# Sheet1.net
KiCad netlist of a schematic drawn in Altium Designer
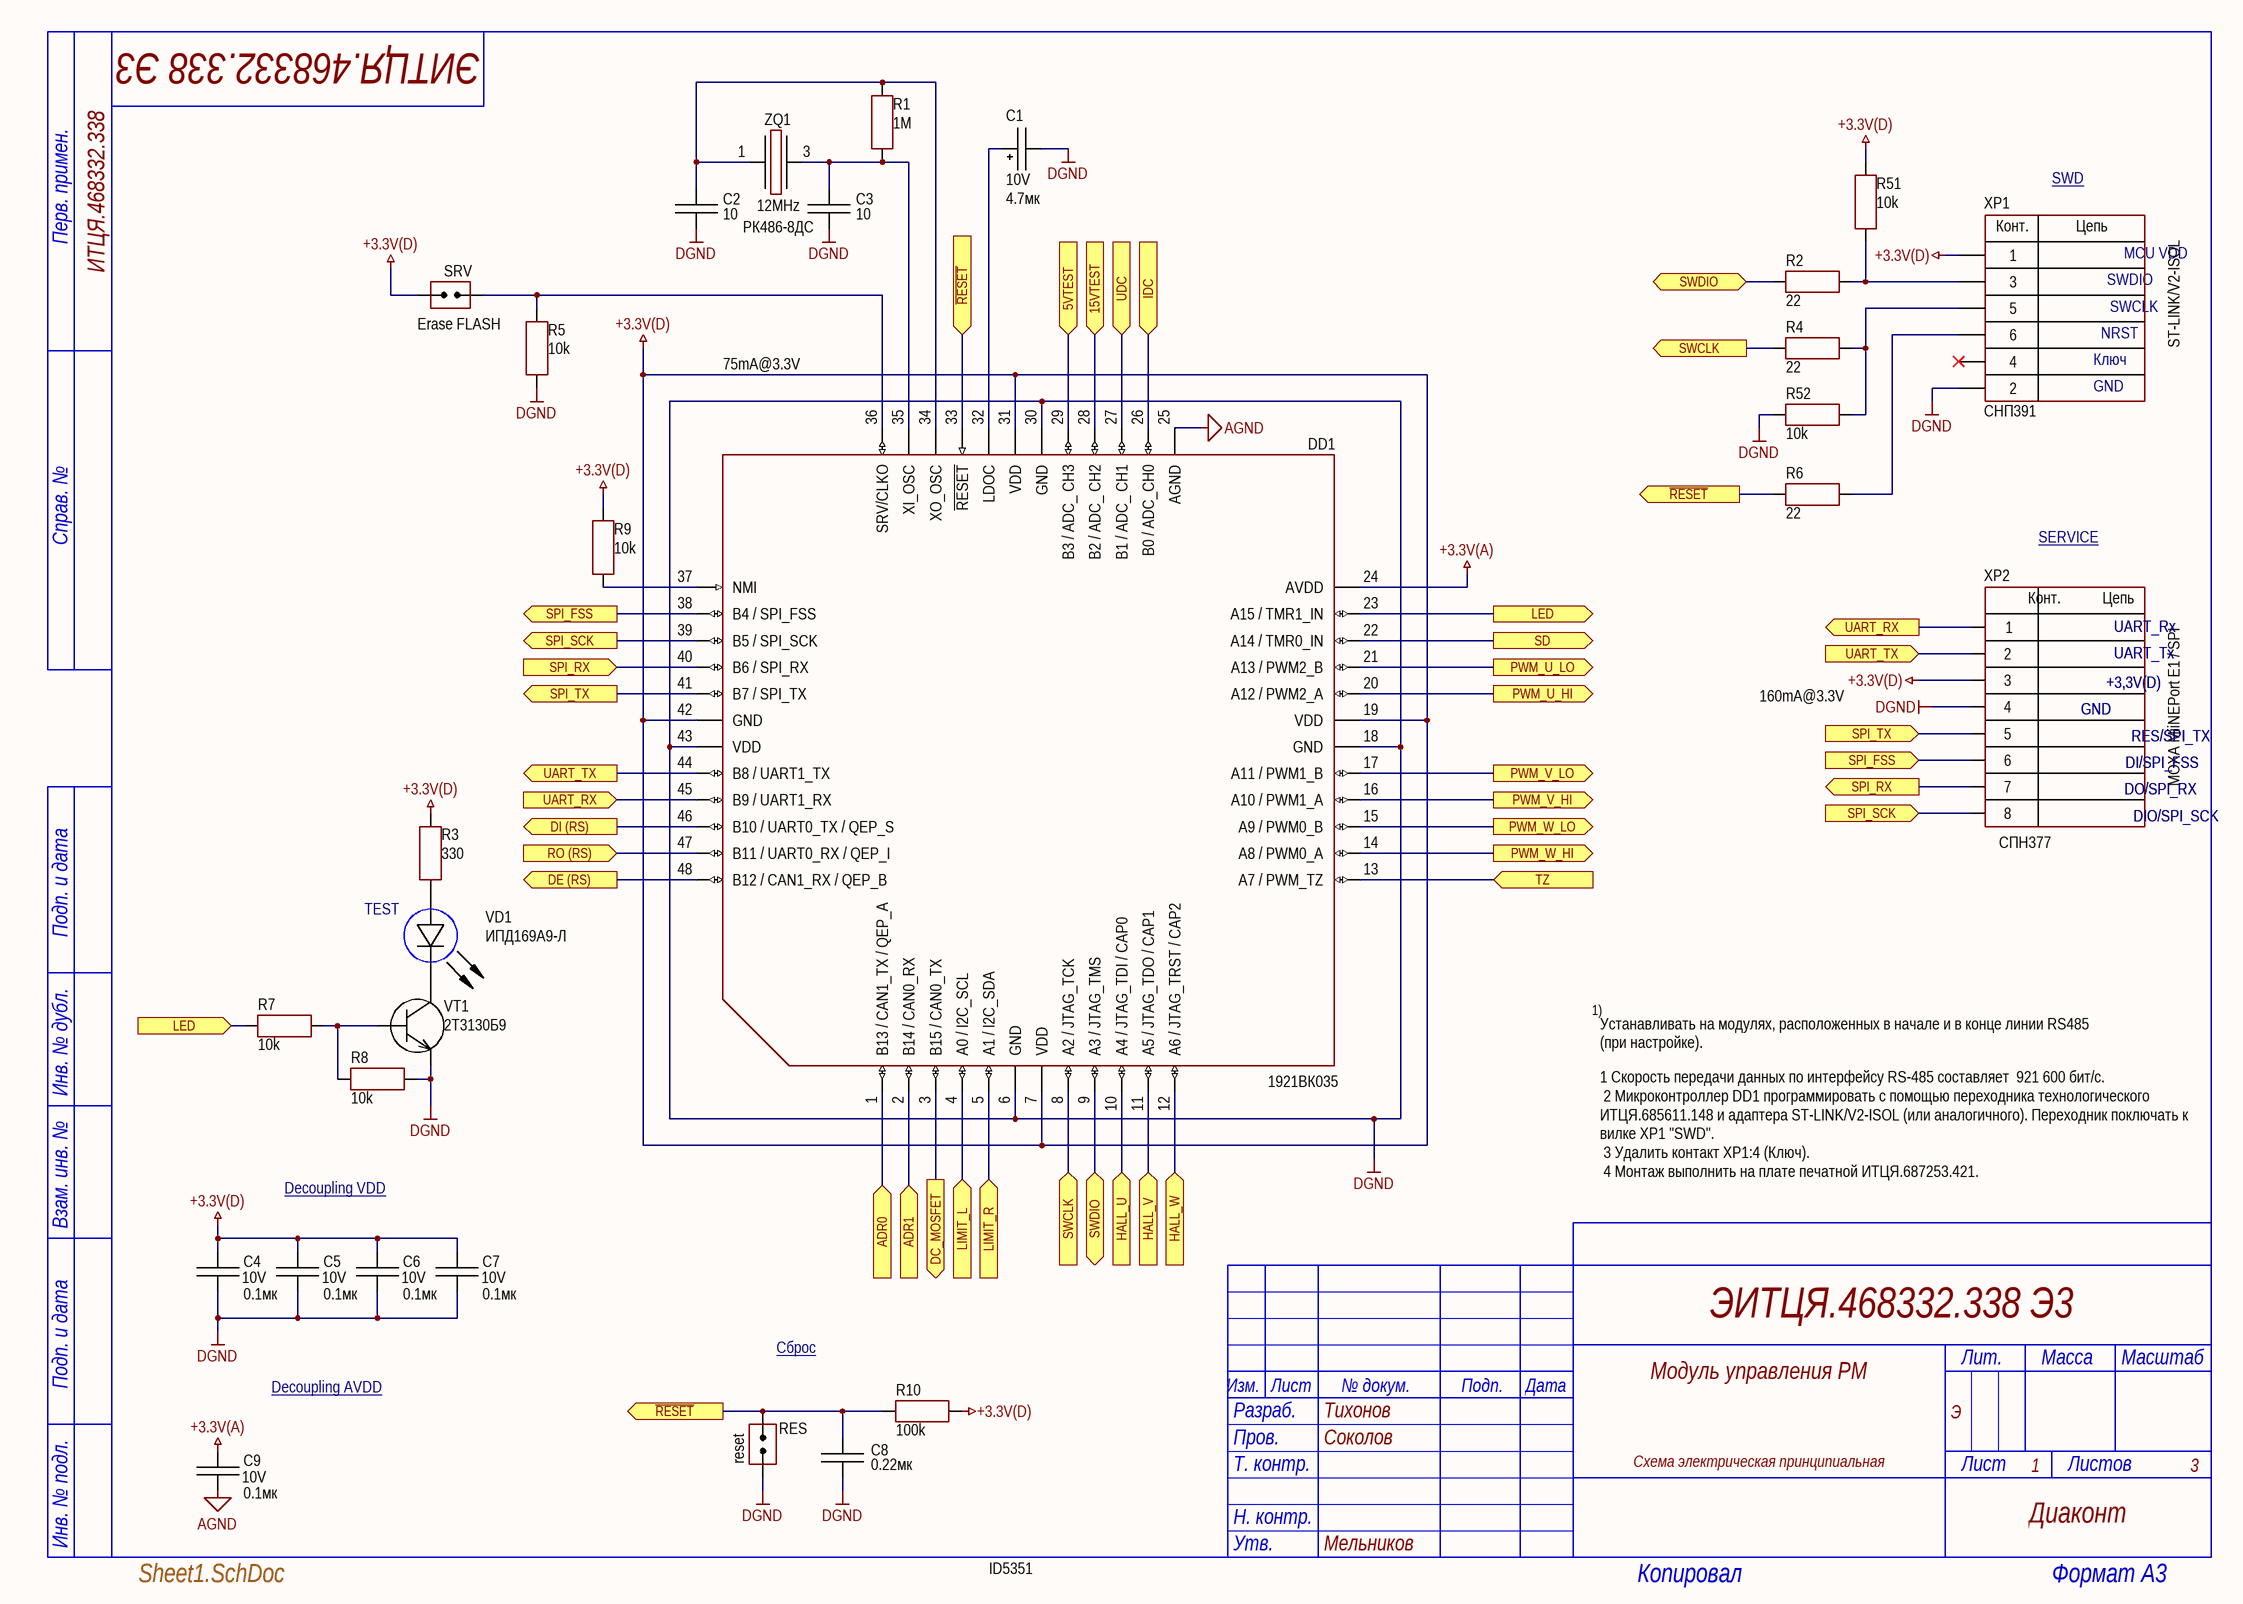
[diagram p0: Sheet1.SchDoc]

(export (version "E")
  (design (tool "Eeschema 10.0.6"))
  (components
    (comp (ref "C1")
      (value "4.7мк")
      (footprint "StandardCase:CAP: TANTAL-A")
      (fields
        (field (name "MANUFACTURER") "Элеконд")
        (field (name "PARTNUMBER") "К53-68 \"А\"-10 В-4.7 мкф")
        (field (name "VALUEMANUFACTURERPARTNUMBER") "Tantalum capacitor, 4.7мк, 10V, ±10%, 2Ohm, case A (3216), -55...+125°C")
        (field (name "VOLTAGE") "10V")
      )
      (libsource (lib "Capacitor") (part "Tantal_A"))
    )
    (comp (ref "C2")
      (value "10")
      (footprint "StandardCase:CAP: 0603P")
      (fields
        (field (name "MANUFACTURER") "Монолит")
        (field (name "PARTNUMBER") "К10-84в-1608М-50В-10 пФ ±5%-МП0-N-A")
        (field (name "VALUEMANUFACTURERPARTNUMBER") "Ceramic capacitor, 10, МП0, ±5%, 50V, 0603, -55...+125°C")
      )
      (libsource (lib "Capacitor") (part "Ceramic_0603"))
    )
    (comp (ref "C3")
      (value "10")
      (footprint "StandardCase:CAP: 0603P")
      (fields
        (field (name "MANUFACTURER") "Монолит")
        (field (name "PARTNUMBER") "К10-84в-1608М-50В-10 пФ ±5%-МП0-N-A")
        (field (name "VALUEMANUFACTURERPARTNUMBER") "Ceramic capacitor, 10, МП0, ±5%, 50V, 0603, -55...+125°C")
      )
      (libsource (lib "Capacitor") (part "Ceramic_0603"))
    )
    (comp (ref "C4")
      (value "0.1мк")
      (footprint "StandardCase:CAP: 0603P")
      (fields
        (field (name "MANUFACTURER") "Гириконд")
        (field (name "PARTNUMBER") "К10-79-10В-0,1 мкФ +80-20% H90")
        (field (name "VALUEMANUFACTURERPARTNUMBER") "Ceramic capacitor, 0.1мк, H90, +80-20%, 10V, 0603, -55...+125°C")
        (field (name "VOLTAGE") "10V")
      )
      (libsource (lib "Capacitor") (part "Ceramic_0603"))
    )
    (comp (ref "C5")
      (value "0.1мк")
      (footprint "StandardCase:CAP: 0603P")
      (fields
        (field (name "MANUFACTURER") "Гириконд")
        (field (name "PARTNUMBER") "К10-79-10В-0,1 мкФ +80-20% H90")
        (field (name "VALUEMANUFACTURERPARTNUMBER") "Ceramic capacitor, 0.1мк, H90, +80-20%, 10V, 0603, -55...+125°C")
        (field (name "VOLTAGE") "10V")
      )
      (libsource (lib "Capacitor") (part "Ceramic_0603"))
    )
    (comp (ref "C6")
      (value "0.1мк")
      (footprint "StandardCase:CAP: 0603P")
      (fields
        (field (name "MANUFACTURER") "Гириконд")
        (field (name "PARTNUMBER") "К10-79-10В-0,1 мкФ +80-20% H90")
        (field (name "VALUEMANUFACTURERPARTNUMBER") "Ceramic capacitor, 0.1мк, H90, +80-20%, 10V, 0603, -55...+125°C")
        (field (name "VOLTAGE") "10V")
      )
      (libsource (lib "Capacitor") (part "Ceramic_0603"))
    )
    (comp (ref "C7")
      (value "0.1мк")
      (footprint "StandardCase:CAP: 0603P")
      (fields
        (field (name "MANUFACTURER") "Гириконд")
        (field (name "PARTNUMBER") "К10-79-10В-0,1 мкФ +80-20% H90")
        (field (name "VALUEMANUFACTURERPARTNUMBER") "Ceramic capacitor, 0.1мк, H90, +80-20%, 10V, 0603, -55...+125°C")
        (field (name "VOLTAGE") "10V")
      )
      (libsource (lib "Capacitor") (part "Ceramic_0603"))
    )
    (comp (ref "C8")
      (value "0.22мк")
      (footprint "StandardCase:CAP: 0805P")
      (fields
        (field (name "MANUFACTURER") "Монолит")
        (field (name "PARTNUMBER") "К10-84в-1608М-25В-220 нФ +80/-20%-Н90-N-A")
        (field (name "VALUEMANUFACTURERPARTNUMBER") "Ceramic capacitor, 0.22мк, H90, +80/-20%, 25V, 0805 (2012M), -55...+125°C")
      )
      (libsource (lib "Capacitor") (part "Ceramic_5750M"))
    )
    (comp (ref "C9")
      (value "0.1мк")
      (footprint "StandardCase:CAP: 0603P")
      (fields
        (field (name "MANUFACTURER") "Гириконд")
        (field (name "PARTNUMBER") "К10-79-10В-0,1 мкФ +80-20% H90")
        (field (name "VALUEMANUFACTURERPARTNUMBER") "Ceramic capacitor, 0.1мк, H90, +80-20%, 10V, 0603, -55...+125°C")
        (field (name "VOLTAGE") "10V")
      )
      (libsource (lib "Capacitor") (part "Ceramic_0603"))
    )
    (comp (ref "DD1")
      (value "~")
      (footprint "48-QLCC (МК 5162.48-1) - small pads")
      (description "Cortex-M4F")
      (fields (field (name "MANUFACTURER") "НИИЭТ") (field (name "PARTNUMBER") "1921ВК035"))
      (libsource (lib "IC. MCU") (part "1921ВК035"))
    )
    (comp (ref "R1")
      (value "1М")
      (footprint "RES: 0603P")
      (fields
        (field (name "MANUFACTURER") "ОАО Ресурс")
        (field (name "PARTNUMBER") "Р1-12-0,1ум.-1~МОм ±5%-М ШКАБ.434110.002 ТУ")
        (field (name "VALUEMANUFACTURERPARTNUMBER") "Resistor film, 1М, ±5%, 0603, 0.1W, -55...+125°C")
      )
      (libsource (lib "Resistor") (part "Resistor_0603"))
    )
    (comp (ref "R2")
      (value "22")
      (footprint "RES: 0603P")
      (fields
        (field (name "MANUFACTURER") "ОАО Ресурс")
        (field (name "PARTNUMBER") "Р1-12-0,1ум.-22~Ом ±5%-М ШКАБ.434110.002 ТУ")
        (field (name "VALUEMANUFACTURERPARTNUMBER") "Resistor film, 22, ±5%, 0603, 0.1W, -55...+125°C")
      )
      (libsource (lib "") (part "Resistor_0603_3"))
    )
    (comp (ref "R3")
      (value "330")
      (footprint "RES: 0603P")
      (fields
        (field (name "MANUFACTURER") "ОАО Ресурс")
        (field (name "PARTNUMBER") "Р1-12-0,1ум.-330~Ом ±5%-М ШКАБ.434110.002 ТУ")
        (field (name "VALUEMANUFACTURERPARTNUMBER") "Resistor film, 330, ±5%, 0603, 0.1W, -55...+125°C")
      )
      (libsource (lib "") (part "Resistor_0603_2"))
    )
    (comp (ref "R4")
      (value "22")
      (footprint "RES: 0603P")
      (fields
        (field (name "MANUFACTURER") "ОАО Ресурс")
        (field (name "PARTNUMBER") "Р1-12-0,1ум.-22~Ом ±5%-М ШКАБ.434110.002 ТУ")
        (field (name "VALUEMANUFACTURERPARTNUMBER") "Resistor film, 22, ±5%, 0603, 0.1W, -55...+125°C")
      )
      (libsource (lib "") (part "Resistor_0603_3"))
    )
    (comp (ref "R5")
      (value "10k")
      (footprint "RES: 0603P")
      (fields
        (field (name "MANUFACTURER") "ОАО Ресурс")
        (field (name "PARTNUMBER") "Р1-12-0,1ум.-10~кОм ±5%-М ШКАБ.434110.002 ТУ")
        (field (name "VALUEMANUFACTURERPARTNUMBER") "Resistor film, 10k, ±5%, 0603, 0.1W, -55...+125°C")
      )
      (libsource (lib "") (part "Resistor_0603_2"))
    )
    (comp (ref "R6")
      (value "22")
      (footprint "RES: 0603P")
      (fields
        (field (name "MANUFACTURER") "ОАО Ресурс")
        (field (name "PARTNUMBER") "Р1-12-0,1ум.-22~Ом ±5%-М ШКАБ.434110.002 ТУ")
        (field (name "VALUEMANUFACTURERPARTNUMBER") "Resistor film, 22, ±5%, 0603, 0.1W, -55...+125°C")
      )
      (libsource (lib "") (part "Resistor_0603_3"))
    )
    (comp (ref "R7")
      (value "10k")
      (footprint "RES: 0603P")
      (fields
        (field (name "MANUFACTURER") "ОАО Ресурс")
        (field (name "PARTNUMBER") "Р1-12-0,1ум.-10~кОм ±5%-М ШКАБ.434110.002 ТУ")
        (field (name "VALUEMANUFACTURERPARTNUMBER") "Resistor film, 10k, ±5%, 0603, 0.1W, -55...+125°C")
      )
      (libsource (lib "") (part "Resistor_0603_1"))
    )
    (comp (ref "R8")
      (value "10k")
      (footprint "RES: 0603P")
      (fields
        (field (name "MANUFACTURER") "ОАО Ресурс")
        (field (name "PARTNUMBER") "Р1-12-0,1ум.-10~кОм ±5%-М ШКАБ.434110.002 ТУ")
        (field (name "VALUEMANUFACTURERPARTNUMBER") "Resistor film, 10k, ±5%, 0603, 0.1W, -55...+125°C")
      )
      (libsource (lib "") (part "Resistor_0603_1"))
    )
    (comp (ref "R9")
      (value "10k")
      (footprint "RES: 0603P")
      (fields
        (field (name "MANUFACTURER") "ОАО Ресурс")
        (field (name "PARTNUMBER") "Р1-12-0,1ум.-10~кОм ±5%-М ШКАБ.434110.002 ТУ")
        (field (name "VALUEMANUFACTURERPARTNUMBER") "Resistor film, 10k, ±5%, 0603, 0.1W, -55...+125°C")
      )
      (libsource (lib "") (part "Resistor_0603_2"))
    )
    (comp (ref "R10")
      (value "100k")
      (footprint "RES: 0603P")
      (fields
        (field (name "MANUFACTURER") "ОАО Ресурс")
        (field (name "PARTNUMBER") "Р1-12-0,1ум.-100~кОм ±5%-М ШКАБ.434110.002 ТУ")
        (field (name "VALUEMANUFACTURERPARTNUMBER") "Resistor film, 100k, ±5%, 0603, 0.1W, -55...+125°C")
      )
      (libsource (lib "") (part "Resistor_0603_3"))
    )
    (comp (ref "R51")
      (value "10k")
      (footprint "RES: 0603P")
      (fields
        (field (name "MANUFACTURER") "ОАО Ресурс")
        (field (name "PARTNUMBER") "Р1-12-0,1ум.-10~кОм ±5%-М ШКАБ.434110.002 ТУ")
        (field (name "VALUEMANUFACTURERPARTNUMBER") "Resistor film, 10k, ±5%, 0603, 0.1W, -55...+125°C")
      )
      (libsource (lib "") (part "Resistor_0603_2"))
    )
    (comp (ref "R52")
      (value "10k")
      (footprint "RES: 0603P")
      (fields
        (field (name "MANUFACTURER") "ОАО Ресурс")
        (field (name "PARTNUMBER") "Р1-12-0,1ум.-10~кОм ±5%-М ШКАБ.434110.002 ТУ")
        (field (name "VALUEMANUFACTURERPARTNUMBER") "Resistor film, 10k, ±5%, 0603, 0.1W, -55...+125°C")
      )
      (libsource (lib "") (part "Resistor_0603_3"))
    )
    (comp (ref "RES")
      (value "~")
      (footprint "CustomCase:CON: JUMPER x1")
      (fields
        (field (name "COMMENTTEXT") "reset")
        (field (name "PARTNUMBER") "СНП377-2ВП21-1-02-04")
        (field (name "MANUFACTURER") "ОАО \"Карачевский завод \"Электродеталь\"")
      )
      (libsource (lib "") (part "Jumper_single_1"))
    )
    (comp (ref "SRV")
      (value "~")
      (footprint "CustomCase:CON: JUMPER x1")
      (fields
        (field (name "COMMENTTEXT") "Erase FLASH")
        (field (name "PARTNUMBER") "СНП391-2ВП21-1 РЮМК.430420.036 ТУ")
        (field (name "MANUFACTURER") "ОАО \"Карачевский завод \"Электродеталь\"")
      )
      (libsource (lib "Connector") (part "Jumper_single"))
    )
    (comp (ref "VD1")
      (value "~")
      (footprint "StandardCase:LED: 0603G")
      (fields
        (field (name "MANUFACTURER") "Протон")
        (field (name "VALUEMANUFACTURERPARTNUMBER") "LED, 20mA max, 2.1V typ, 1608, -55...+150°C")
        (field (name "PARTNUMBER") "ИПД169А9-Л")
        (field (name "COMMENTTEXT") "TEST")
      )
      (libsource (lib "Diode") (part "LED_single"))
    )
    (comp (ref "VT1")
      (value "~")
      (footprint "SOT23")
      (fields
        (field (name "MANUFACTURER") "ООО НПК Далекс")
        (field (name "VALUEMANUFACTURERPARTNUMBER") "NPN transistor, 30V, 100mA, , 300mW, 0.7V, 500, SOT-23 (КТ-46), -55...+125°C")
        (field (name "PARTNUMBER") "2Т3130Б9")
      )
      (libsource (lib "Transistor") (part "BJT_NPN_132"))
    )
    (comp (ref "XP1")
      (value "SWD")
      (footprint "CON: PLLD-6-S")
      (description "аналог СНП391-6ВП41-2")
      (fields
        (field (name "MANUFACTURER") "Электроделать")
        (field (name "VALUEMANUFACTURERPARTNUMBER") "Connector, 6pin, 1.27mm, 125VAC, 1A")
        (field (name "COMMENTTEXT") "СНП391")
      )
      (libsource (lib "Connector") (part "PLLD1.27-6_1"))
    )
    (comp (ref "XP2")
      (value "SERVICE")
      (footprint "CON: PLD2-8-S")
      (description "СНП377-8ВП41-2 SMD")
      (fields
        (field (name "MANUFACTURER") "ОАО \"Карачевский завод \"Электродеталь\"")
        (field (name "PARTNUMBER") "СНП377-8ВП41-2")
        (field (name "COMMENTTEXT") "СПН377")
      )
      (libsource (lib "Connector") (part "PLD2-8-S"))
    )
    (comp (ref "ZQ1")
      (value "~")
      (footprint "CustomCase:OSC: 5070G")
      (fields
        (field (name "MANUFACTURER") "ОАО \"Морион\"")
        (field (name "PARTNUMBER") "РК486-8ДС-12000K")
        (field (name "VALUEMANUFACTURERPARTNUMBER") "Oscilator, 12MHz, CMOS, ±30ppm, case 5070, -40...+85°C")
        (field (name "FREQUENCY") "12MHz")
        (field (name "COMMENTPART") "РК486-8ДС")
      )
      (libsource (lib "Oscilator") (part "Oscilator_5070"))
    )
  )
  (nets
    (net (code "1") (name "+3.3V(A)") (class "Default")
      (node (ref "C9") (pin "2") (pinfunction "2_2") (pintype "passive"))
      (node (ref "DD1") (pin "24") (pinfunction "AVDD_24") (pintype "power_in"))
    )
    (net (code "2") (name "+3.3V(D)") (class "Default")
      (node (ref "C4") (pin "2") (pinfunction "2_2") (pintype "passive"))
      (node (ref "C5") (pin "2") (pinfunction "2_2") (pintype "passive"))
      (node (ref "C6") (pin "2") (pinfunction "2_2") (pintype "passive"))
      (node (ref "C7") (pin "2") (pinfunction "2_2") (pintype "passive"))
      (node (ref "DD1") (pin "19") (pinfunction "VDD_19") (pintype "power_in"))
      (node (ref "DD1") (pin "31") (pinfunction "VDD_31") (pintype "power_in"))
      (node (ref "DD1") (pin "42") (pinfunction "GND_42") (pintype "power_in"))
      (node (ref "DD1") (pin "7") (pinfunction "VDD_7") (pintype "power_in"))
      (node (ref "R10") (pin "2") (pinfunction "2_2") (pintype "passive"))
      (node (ref "R3") (pin "1") (pinfunction "1_1") (pintype "passive"))
      (node (ref "R51") (pin "1") (pinfunction "1_1") (pintype "passive"))
      (node (ref "R9") (pin "1") (pinfunction "1_1") (pintype "passive"))
      (node (ref "SRV") (pin "1") (pinfunction "IN_1") (pintype "passive"))
      (node (ref "XP1") (pin "1") (pinfunction "1_1") (pintype "passive"))
      (node (ref "XP2") (pin "3") (pinfunction "3_3") (pintype "passive"))
    )
    (net (code "3") (name "/5VTEST") (class "Default")
      (node (ref "DD1") (pin "29") (pinfunction "B3_/_ADC__CH3_29") (pintype "bidirectional"))
    )
    (net (code "4") (name "/15VTEST") (class "Default")
      (node (ref "DD1") (pin "28") (pinfunction "B2_/_ADC__CH2_28") (pintype "bidirectional"))
    )
    (net (code "5") (name "/ADR0") (class "Default")
      (node (ref "DD1") (pin "1") (pinfunction "B13_/_CAN1_TX_/_QEP_A_1") (pintype "bidirectional"))
    )
    (net (code "6") (name "/ADR1") (class "Default")
      (node (ref "DD1") (pin "2") (pinfunction "B14_/_CAN0_RX_2") (pintype "bidirectional"))
    )
    (net (code "7") (name "/DC_MOSFET") (class "Default")
      (node (ref "DD1") (pin "3") (pinfunction "B15_/_CAN0_TX_3") (pintype "bidirectional"))
    )
    (net (code "8") (name "/DE (RS)") (class "Default")
      (node (ref "DD1") (pin "48") (pinfunction "B12_/_CAN1_RX_/_QEP_B_48") (pintype "bidirectional"))
    )
    (net (code "9") (name "/DI (RS)") (class "Default")
      (node (ref "DD1") (pin "46") (pinfunction "B10_/_UART0_TX_/_QEP_S_46") (pintype "bidirectional"))
    )
    (net (code "10") (name "/HALL_U") (class "Default")
      (node (ref "DD1") (pin "10") (pinfunction "A4_/_JTAG_TDI_/_CAP0_10") (pintype "bidirectional"))
    )
    (net (code "11") (name "/HALL_V") (class "Default")
      (node (ref "DD1") (pin "11") (pinfunction "A5_/_JTAG_TDO_/_CAP1_11") (pintype "bidirectional"))
    )
    (net (code "12") (name "/HALL_W") (class "Default")
      (node (ref "DD1") (pin "12") (pinfunction "A6_/_JTAG_TRST_/_CAP2_12") (pintype "bidirectional"))
    )
    (net (code "13") (name "/IDC") (class "Default")
      (node (ref "DD1") (pin "26") (pinfunction "B0_/_ADC_CH0_26") (pintype "bidirectional"))
    )
    (net (code "14") (name "/LED") (class "Default")
      (node (ref "DD1") (pin "23") (pinfunction "A15_/_TMR1_IN_23") (pintype "bidirectional"))
      (node (ref "R7") (pin "2") (pinfunction "2_2") (pintype "passive"))
    )
    (net (code "15") (name "/LIMIT_L") (class "Default")
      (node (ref "DD1") (pin "4") (pinfunction "A0_/_I2C_SCL_4") (pintype "bidirectional"))
    )
    (net (code "16") (name "/LIMIT_R") (class "Default")
      (node (ref "DD1") (pin "5") (pinfunction "A1_/_I2C_SDA_5") (pintype "bidirectional"))
    )
    (net (code "17") (name "/PWM_U_HI") (class "Default")
      (node (ref "DD1") (pin "20") (pinfunction "A12_/_PWM2_A_20") (pintype "bidirectional"))
    )
    (net (code "18") (name "/PWM_U_LO") (class "Default")
      (node (ref "DD1") (pin "21") (pinfunction "A13_/_PWM2_B_21") (pintype "bidirectional"))
    )
    (net (code "19") (name "/PWM_V_HI") (class "Default")
      (node (ref "DD1") (pin "16") (pinfunction "A10_/_PWM1_A_16") (pintype "bidirectional"))
    )
    (net (code "20") (name "/PWM_V_LO") (class "Default")
      (node (ref "DD1") (pin "17") (pinfunction "A11_/_PWM1_B_17") (pintype "bidirectional"))
    )
    (net (code "21") (name "/PWM_W_HI") (class "Default")
      (node (ref "DD1") (pin "14") (pinfunction "A8_/_PWM0_A_14") (pintype "bidirectional"))
    )
    (net (code "22") (name "/PWM_W_LO") (class "Default")
      (node (ref "DD1") (pin "15") (pinfunction "A9_/_PWM0_B_15") (pintype "bidirectional"))
    )
    (net (code "23") (name "/RO (RS)") (class "Default")
      (node (ref "DD1") (pin "47") (pinfunction "B11_/_UART0_RX_/_QEP_I_47") (pintype "bidirectional"))
    )
    (net (code "24") (name "/SD") (class "Default")
      (node (ref "DD1") (pin "22") (pinfunction "A14_/_TMR0_IN_22") (pintype "bidirectional"))
    )
    (net (code "25") (name "/SPI_FSS") (class "Default")
      (node (ref "DD1") (pin "38") (pinfunction "B4_/_SPI_FSS_38") (pintype "bidirectional"))
      (node (ref "XP2") (pin "6") (pinfunction "6_6") (pintype "passive"))
    )
    (net (code "26") (name "/SPI_RX") (class "Default")
      (node (ref "DD1") (pin "40") (pinfunction "B6_/_SPI_RX_40") (pintype "bidirectional"))
      (node (ref "XP2") (pin "7") (pinfunction "7_7") (pintype "passive"))
    )
    (net (code "27") (name "/SPI_SCK") (class "Default")
      (node (ref "DD1") (pin "39") (pinfunction "B5_/_SPI_SCK_39") (pintype "bidirectional"))
      (node (ref "XP2") (pin "8") (pinfunction "8_8") (pintype "passive"))
    )
    (net (code "28") (name "/SPI_TX") (class "Default")
      (node (ref "DD1") (pin "41") (pinfunction "B7_/_SPI_TX_41") (pintype "bidirectional"))
      (node (ref "XP2") (pin "5") (pinfunction "5_5") (pintype "passive"))
    )
    (net (code "29") (name "/SWCLK") (class "Default")
      (node (ref "DD1") (pin "8") (pinfunction "A2_/_JTAG_TCK_8") (pintype "bidirectional"))
      (node (ref "R4") (pin "1") (pinfunction "1_1") (pintype "passive"))
    )
    (net (code "30") (name "/SWDIO") (class "Default")
      (node (ref "DD1") (pin "9") (pinfunction "A3_/_JTAG_TMS_9") (pintype "bidirectional"))
      (node (ref "R2") (pin "1") (pinfunction "1_1") (pintype "passive"))
    )
    (net (code "31") (name "/TZ") (class "Default")
      (node (ref "DD1") (pin "13") (pinfunction "A7_/_PWM_TZ_13") (pintype "bidirectional"))
    )
    (net (code "32") (name "/UART_RX") (class "Default")
      (node (ref "DD1") (pin "45") (pinfunction "B9_/_UART1_RX_45") (pintype "bidirectional"))
      (node (ref "XP2") (pin "1") (pinfunction "1_1") (pintype "passive"))
    )
    (net (code "33") (name "/UART_TX") (class "Default")
      (node (ref "DD1") (pin "44") (pinfunction "B8_/_UART1_TX_44") (pintype "bidirectional"))
      (node (ref "XP2") (pin "2") (pinfunction "2_2") (pintype "passive"))
    )
    (net (code "34") (name "/UDC") (class "Default")
      (node (ref "DD1") (pin "27") (pinfunction "B1_/_ADC__CH1_27") (pintype "bidirectional"))
    )
    (net (code "35") (name "/~{RESET}") (class "Default")
      (node (ref "C8") (pin "2") (pinfunction "2_2") (pintype "passive"))
      (node (ref "DD1") (pin "33") (pinfunction "~{RESET}_33") (pintype "input"))
      (node (ref "R10") (pin "1") (pinfunction "1_1") (pintype "passive"))
      (node (ref "R6") (pin "1") (pinfunction "1_1") (pintype "passive"))
      (node (ref "RES") (pin "2") (pinfunction "IN_2") (pintype "passive"))
    )
    (net (code "36") (name "AGND") (class "Default")
      (node (ref "C9") (pin "1") (pinfunction "1_1") (pintype "passive"))
      (node (ref "DD1") (pin "25") (pinfunction "AGND_25") (pintype "power_in"))
    )
    (net (code "37") (name "DGND") (class "Default")
      (node (ref "C1") (pin "2") (pinfunction "2_2") (pintype "passive"))
      (node (ref "C2") (pin "2") (pinfunction "2_2") (pintype "passive"))
      (node (ref "C3") (pin "2") (pinfunction "2_2") (pintype "passive"))
      (node (ref "C4") (pin "1") (pinfunction "1_1") (pintype "passive"))
      (node (ref "C5") (pin "1") (pinfunction "1_1") (pintype "passive"))
      (node (ref "C6") (pin "1") (pinfunction "1_1") (pintype "passive"))
      (node (ref "C7") (pin "1") (pinfunction "1_1") (pintype "passive"))
      (node (ref "C8") (pin "1") (pinfunction "1_1") (pintype "passive"))
      (node (ref "DD1") (pin "18") (pinfunction "GND_18") (pintype "power_in"))
      (node (ref "DD1") (pin "30") (pinfunction "GND_30") (pintype "power_in"))
      (node (ref "DD1") (pin "43") (pinfunction "VDD_43") (pintype "power_in"))
      (node (ref "DD1") (pin "6") (pinfunction "GND_6") (pintype "power_in"))
      (node (ref "R5") (pin "2") (pinfunction "2_2") (pintype "passive"))
      (node (ref "R52") (pin "1") (pinfunction "1_1") (pintype "passive"))
      (node (ref "R8") (pin "1") (pinfunction "1_1") (pintype "passive"))
      (node (ref "RES") (pin "1") (pinfunction "IN_1") (pintype "passive"))
      (node (ref "VT1") (pin "2") (pinfunction "E_2") (pintype "passive"))
      (node (ref "XP1") (pin "2") (pinfunction "2_2") (pintype "passive"))
      (node (ref "XP2") (pin "4") (pinfunction "4_4") (pintype "passive"))
    )
    (net (code "38") (name "Net-(DD1-LDOC)") (class "Default")
      (node (ref "C1") (pin "1") (pinfunction "1_1") (pintype "passive"))
      (node (ref "DD1") (pin "32") (pinfunction "LDOC_32") (pintype "passive"))
    )
    (net (code "39") (name "Net-(DD1-NMI)") (class "Default")
      (node (ref "DD1") (pin "37") (pinfunction "NMI_37") (pintype "input"))
      (node (ref "R9") (pin "2") (pinfunction "2_2") (pintype "passive"))
    )
    (net (code "40") (name "Net-(DD1-SRV{slash}CLKO)") (class "Default")
      (node (ref "DD1") (pin "36") (pinfunction "SRV/CLKO_36") (pintype "bidirectional"))
      (node (ref "R5") (pin "1") (pinfunction "1_1") (pintype "passive"))
      (node (ref "SRV") (pin "2") (pinfunction "IN_2") (pintype "passive"))
    )
    (net (code "41") (name "Net-(DD1-XI_OSC)") (class "Default")
      (node (ref "C3") (pin "1") (pinfunction "1_1") (pintype "passive"))
      (node (ref "DD1") (pin "35") (pinfunction "XI_OSC_35") (pintype "passive"))
      (node (ref "R1") (pin "1") (pinfunction "1_1") (pintype "passive"))
      (node (ref "ZQ1") (pin "3") (pinfunction "3_3") (pintype "passive"))
    )
    (net (code "42") (name "Net-(DD1-XO_OSC)") (class "Default")
      (node (ref "C2") (pin "1") (pinfunction "1_1") (pintype "passive"))
      (node (ref "DD1") (pin "34") (pinfunction "XO_OSC_34") (pintype "passive"))
      (node (ref "R1") (pin "2") (pinfunction "2_2") (pintype "passive"))
      (node (ref "ZQ1") (pin "1") (pinfunction "1_1") (pintype "passive"))
    )
    (net (code "43") (name "Net-(R2-Pad2)") (class "Default")
      (node (ref "R2") (pin "2") (pinfunction "2_2") (pintype "passive"))
      (node (ref "R51") (pin "2") (pinfunction "2_2") (pintype "passive"))
      (node (ref "XP1") (pin "3") (pinfunction "3_3") (pintype "power_in"))
    )
    (net (code "44") (name "Net-(R4-Pad2)") (class "Default")
      (node (ref "R4") (pin "2") (pinfunction "2_2") (pintype "passive"))
      (node (ref "R52") (pin "2") (pinfunction "2_2") (pintype "passive"))
      (node (ref "XP1") (pin "5") (pinfunction "5_5") (pintype "power_in"))
    )
    (net (code "45") (name "Net-(R6-Pad2)") (class "Default")
      (node (ref "R6") (pin "2") (pinfunction "2_2") (pintype "passive"))
      (node (ref "XP1") (pin "6") (pinfunction "6_6") (pintype "power_in"))
    )
    (net (code "46") (name "Net-(VD1-A)") (class "Default")
      (node (ref "R3") (pin "2") (pinfunction "2_2") (pintype "passive"))
      (node (ref "VD1") (pin "1") (pinfunction "A_1") (pintype "passive"))
    )
    (net (code "47") (name "Net-(VD1-C)") (class "Default")
      (node (ref "VD1") (pin "2") (pinfunction "C_2") (pintype "passive"))
      (node (ref "VT1") (pin "3") (pinfunction "C_3") (pintype "passive"))
    )
    (net (code "48") (name "Net-(VT1-B)") (class "Default")
      (node (ref "R7") (pin "1") (pinfunction "1_1") (pintype "passive"))
      (node (ref "R8") (pin "2") (pinfunction "2_2") (pintype "passive"))
      (node (ref "VT1") (pin "1") (pinfunction "B_1") (pintype "passive"))
    )
    (net (code "49") (name "unconnected-(XP1-Pad4)") (class "Default")
      (node (ref "XP1") (pin "4") (pinfunction "4_4") (pintype "power_in+no_connect"))
    )
  )
)
